# Main.net
KiCad netlist of a schematic drawn in Altium Designer
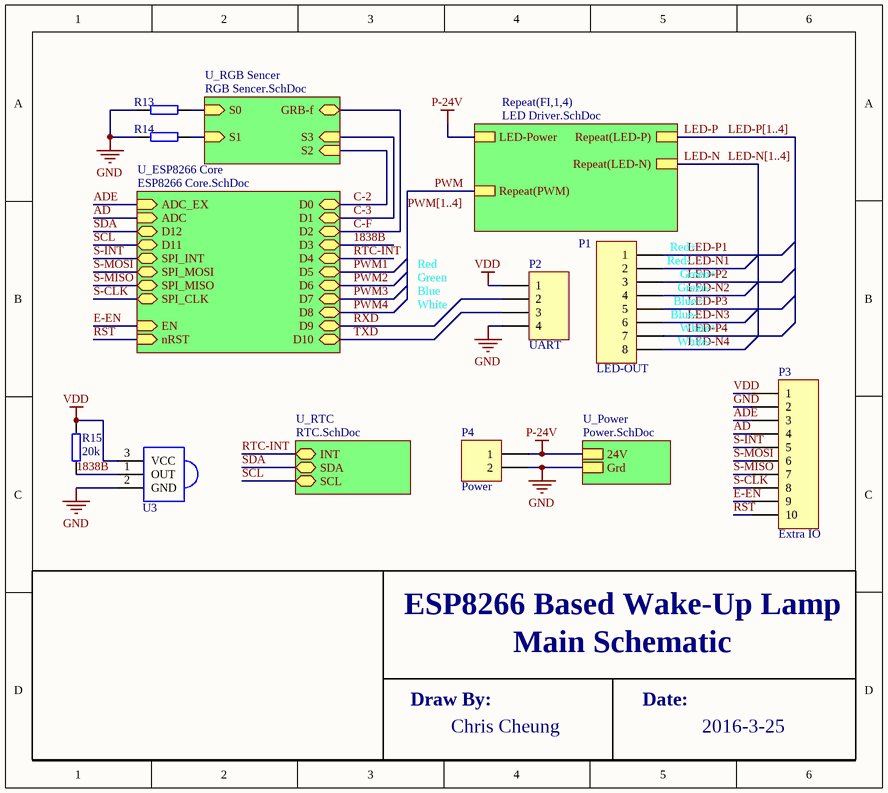
[diagram p0: Main.SchDoc]

(export (version "E")
  (design (tool "Eeschema 10.0.6"))
  (components
    (comp (ref "P1")
      (value "LED-OUT")
      (footprint "HDR1X8H")
      (description "Header, 8-Pin, Right Angle")
      (fields (field (name "PUBLISHER") "Altium Limited"))
      (libsource (lib "Miscellaneous Connectors") (part "Header 8H"))
    )
    (comp (ref "P2")
      (value "UART")
      (footprint "HDR1X4H")
      (description "Header, 4-Pin, Right Angle")
      (fields (field (name "PUBLISHER") "Altium Limited"))
      (libsource (lib "Miscellaneous Connectors") (part "Header 4H"))
    )
    (comp (ref "P3")
      (value "Extra IO")
      (footprint "HDR1X10H")
      (description "Header, 10-Pin, Right Angle")
      (fields (field (name "PUBLISHER") "Altium Limited"))
      (libsource (lib "Miscellaneous Connectors") (part "Header 10H"))
    )
    (comp (ref "P4")
      (value "Power")
      (footprint "HDR1X2")
      (description "Header, 2-Pin")
      (fields (field (name "PUBLISHER") "Altium Limited"))
      (libsource (lib "Miscellaneous Connectors") (part "Header 2"))
    )
    (comp (ref "R13")
      (value "0Ohm")
      (footprint "SMT_R_0402")
      (description "Surface mount resistor 0402")
      (libsource (lib "Vowstar_Basic_Device") (part "SMT_R_0402"))
    )
    (comp (ref "R14")
      (value "0Ohm")
      (footprint "SMT_R_0402")
      (description "Surface mount resistor 0402")
      (libsource (lib "Vowstar_Basic_Device") (part "SMT_R_0402"))
    )
    (comp (ref "R15")
      (value "20k")
      (footprint "SMT_R_0402")
      (description "Surface mount resistor 0402")
      (libsource (lib "Vowstar_Basic_Device") (part "SMT_R_0402"))
    )
    (comp (ref "U3")
      (value "Infrared In-VS1838")
      (description "Infrared In")
      (libsource (lib "Schlib1") (part "VS1838"))
    )
  )
  (nets
    (net (code "1") (name "/1838B") (class "Default")
      (node (ref "R15") (pin "1") (pinfunction "1_1") (pintype "passive"))
      (node (ref "U3") (pin "1") (pinfunction "OUT_1") (pintype "passive"))
    )
    (net (code "2") (name "/AD") (class "Default")
      (node (ref "P3") (pin "4") (pinfunction "4_4") (pintype "passive"))
    )
    (net (code "3") (name "/ADE") (class "Default")
      (node (ref "P3") (pin "3") (pinfunction "3_3") (pintype "passive"))
    )
    (net (code "7") (name "/E-EN") (class "Default")
      (node (ref "P3") (pin "9") (pinfunction "9_9") (pintype "passive"))
    )
    (net (code "9") (name "/LED-N1") (class "Default")
      (node (ref "P1") (pin "2") (pinfunction "2_2") (pintype "passive"))
    )
    (net (code "10") (name "/LED-N2") (class "Default")
      (node (ref "P1") (pin "4") (pinfunction "4_4") (pintype "passive"))
    )
    (net (code "11") (name "/LED-N3") (class "Default")
      (node (ref "P1") (pin "6") (pinfunction "6_6") (pintype "passive"))
    )
    (net (code "12") (name "/LED-N4") (class "Default")
      (node (ref "P1") (pin "8") (pinfunction "8_8") (pintype "passive"))
    )
    (net (code "15") (name "/LED-P1") (class "Default")
      (node (ref "P1") (pin "1") (pinfunction "1_1") (pintype "passive"))
    )
    (net (code "16") (name "/LED-P2") (class "Default")
      (node (ref "P1") (pin "3") (pinfunction "3_3") (pintype "passive"))
    )
    (net (code "17") (name "/LED-P3") (class "Default")
      (node (ref "P1") (pin "5") (pinfunction "5_5") (pintype "passive"))
    )
    (net (code "18") (name "/LED-P4") (class "Default")
      (node (ref "P1") (pin "7") (pinfunction "7_7") (pintype "passive"))
    )
    (net (code "26") (name "/RST") (class "Default")
      (node (ref "P3") (pin "10") (pinfunction "10_10") (pintype "passive"))
    )
    (net (code "28") (name "/RXD") (class "Default")
      (node (ref "P2") (pin "2") (pinfunction "2_2") (pintype "passive"))
    )
    (net (code "29") (name "/S-CLK") (class "Default")
      (node (ref "P3") (pin "8") (pinfunction "8_8") (pintype "passive"))
    )
    (net (code "30") (name "/S-INT") (class "Default")
      (node (ref "P3") (pin "5") (pinfunction "5_5") (pintype "passive"))
    )
    (net (code "31") (name "/S-MISO") (class "Default")
      (node (ref "P3") (pin "7") (pinfunction "7_7") (pintype "passive"))
    )
    (net (code "32") (name "/S-MOSI") (class "Default")
      (node (ref "P3") (pin "6") (pinfunction "6_6") (pintype "passive"))
    )
    (net (code "33") (name "/S0") (class "Default")
      (node (ref "R13") (pin "2") (pinfunction "2_2") (pintype "passive"))
    )
    (net (code "34") (name "/S1") (class "Default")
      (node (ref "R14") (pin "2") (pinfunction "2_2") (pintype "passive"))
    )
    (net (code "37") (name "/TXD") (class "Default")
      (node (ref "P2") (pin "3") (pinfunction "3_3") (pintype "passive"))
    )
    (net (code "38") (name "GND") (class "Default")
      (node (ref "P2") (pin "4") (pinfunction "4_4") (pintype "passive"))
      (node (ref "P3") (pin "2") (pinfunction "2_2") (pintype "passive"))
      (node (ref "P4") (pin "2") (pinfunction "2_2") (pintype "passive"))
      (node (ref "R13") (pin "1") (pinfunction "1_1") (pintype "passive"))
      (node (ref "R14") (pin "1") (pinfunction "1_1") (pintype "passive"))
      (node (ref "U3") (pin "2") (pinfunction "GND_2") (pintype "passive"))
    )
    (net (code "39") (name "P-24V") (class "Default")
      (node (ref "P4") (pin "1") (pinfunction "1_1") (pintype "passive"))
    )
    (net (code "40") (name "VDD") (class "Default")
      (node (ref "P2") (pin "1") (pinfunction "1_1") (pintype "passive"))
      (node (ref "P3") (pin "1") (pinfunction "1_1") (pintype "passive"))
      (node (ref "R15") (pin "2") (pinfunction "2_2") (pintype "passive"))
      (node (ref "U3") (pin "3") (pinfunction "VCC_3") (pintype "passive"))
    )
  )
)
